# 03_Mos.net
KiCad netlist of a schematic drawn in Altium Designer
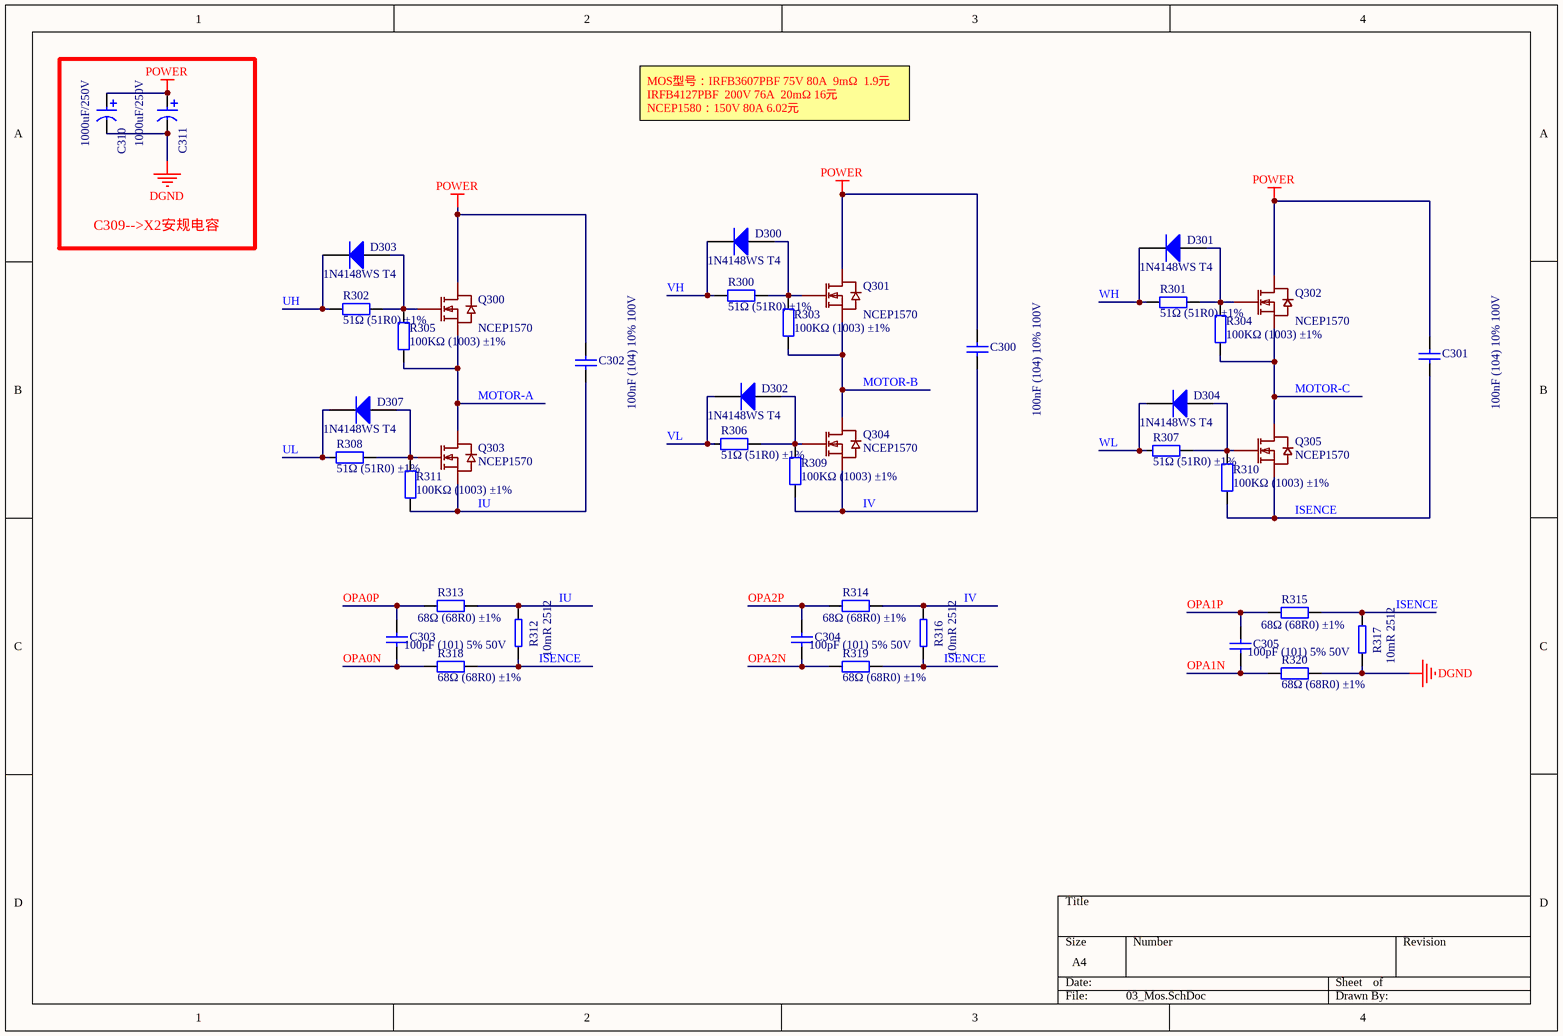
[diagram p0: 03_Mos.SchDoc]

(export (version "E")
  (design (tool "Eeschema 10.0.6"))
  (components
    (comp (ref "C300")
      (value "100nF (104) 10% 100V")
      (footprint "1206_C")
      (description "贴片电容")
      (libsource (lib "Miscellaneous Devices LC") (part "1206 100nF (104) 10% 50V"))
    )
    (comp (ref "C301")
      (value "100nF (104) 10% 100V")
      (footprint "1206_C")
      (description "贴片电容")
      (libsource (lib "Miscellaneous Devices LC") (part "1206 100nF (104) 10% 50V"))
    )
    (comp (ref "C302")
      (value "100nF (104) 10% 100V")
      (footprint "1206_C")
      (description "贴片电容")
      (libsource (lib "Miscellaneous Devices LC") (part "1206 100nF (104) 10% 50V"))
    )
    (comp (ref "C303")
      (value "100pF (101) 5% 50V")
      (footprint "0805_C")
      (description "贴片电容")
      (libsource (lib "Miscellaneous Devices LC") (part "0805 100pF (101) 5% 50V"))
    )
    (comp (ref "C304")
      (value "100pF (101) 5% 50V")
      (footprint "0805_C")
      (description "贴片电容")
      (libsource (lib "Miscellaneous Devices LC") (part "0805 100pF (101) 5% 50V"))
    )
    (comp (ref "C305")
      (value "100pF (101) 5% 50V")
      (footprint "0805_C")
      (description "贴片电容")
      (libsource (lib "Miscellaneous Devices LC") (part "0805 100pF (101) 5% 50V"))
    )
    (comp (ref "C310")
      (value "1000uF/250V")
      (footprint "1000uf/250V")
      (description "电解电容")
      (libsource (lib "Schlibv2") (part "CAP2"))
    )
    (comp (ref "C311")
      (value "1000uF/250V")
      (footprint "1000uf/250V")
      (description "电解电容")
      (libsource (lib "Schlibv2") (part "CAP2"))
    )
    (comp (ref "D300")
      (value "1N4148WS T4")
      (footprint "SOD-323")
      (description "二极管")
      (libsource (lib "Miscellaneous Devices LC") (part "SOD-323 1N4148WS T4"))
    )
    (comp (ref "D301")
      (value "1N4148WS T4")
      (footprint "SOD-323")
      (description "二极管")
      (libsource (lib "Miscellaneous Devices LC") (part "SOD-323 1N4148WS T4"))
    )
    (comp (ref "D302")
      (value "1N4148WS T4")
      (footprint "SOD-323")
      (description "二极管")
      (libsource (lib "Miscellaneous Devices LC") (part "SOD-323 1N4148WS T4"))
    )
    (comp (ref "D303")
      (value "1N4148WS T4")
      (footprint "SOD-323")
      (description "二极管")
      (libsource (lib "Miscellaneous Devices LC") (part "SOD-323 1N4148WS T4"))
    )
    (comp (ref "D304")
      (value "1N4148WS T4")
      (footprint "SOD-323")
      (description "二极管")
      (libsource (lib "Miscellaneous Devices LC") (part "SOD-323 1N4148WS T4"))
    )
    (comp (ref "D307")
      (value "1N4148WS T4")
      (footprint "SOD-323")
      (description "二极管")
      (libsource (lib "Miscellaneous Devices LC") (part "SOD-323 1N4148WS T4"))
    )
    (comp (ref "Q300")
      (value "NCEP1570")
      (footprint "IRFB4127")
      (libsource (lib "RayPCB20210502") (part "IRFB4127PBF"))
    )
    (comp (ref "Q301")
      (value "NCEP1570")
      (footprint "IRFB4127")
      (libsource (lib "RayPCB20210502") (part "IRFB4127PBF"))
    )
    (comp (ref "Q302")
      (value "NCEP1570")
      (footprint "IRFB4127")
      (libsource (lib "RayPCB20210502") (part "IRFB4127PBF"))
    )
    (comp (ref "Q303")
      (value "NCEP1570")
      (footprint "IRFB4127")
      (libsource (lib "RayPCB20210502") (part "IRFB4127PBF"))
    )
    (comp (ref "Q304")
      (value "NCEP1570")
      (footprint "IRFB4127")
      (libsource (lib "RayPCB20210502") (part "IRFB4127PBF"))
    )
    (comp (ref "Q305")
      (value "NCEP1570")
      (footprint "IRFB4127")
      (libsource (lib "RayPCB20210502") (part "IRFB4127PBF"))
    )
    (comp (ref "R300")
      (value "51Ω (51R0) ±1%")
      (footprint "0805_R")
      (description "贴片电阻")
      (libsource (lib "Miscellaneous Devices LC") (part "0805 51Ω (51R0) 1%"))
    )
    (comp (ref "R301")
      (value "51Ω (51R0) ±1%")
      (footprint "0805_R")
      (description "贴片电阻")
      (libsource (lib "Miscellaneous Devices LC") (part "0805 51Ω (51R0) 1%"))
    )
    (comp (ref "R302")
      (value "51Ω (51R0) ±1%")
      (footprint "0805_R")
      (description "贴片电阻")
      (libsource (lib "Miscellaneous Devices LC") (part "0805 51Ω (51R0) 1%"))
    )
    (comp (ref "R303")
      (value "100KΩ (1003) ±1%")
      (footprint "0805_R")
      (description "贴片电阻")
      (libsource (lib "Miscellaneous Devices LC") (part "0805 100KΩ (1003) 1%"))
    )
    (comp (ref "R304")
      (value "100KΩ (1003) ±1%")
      (footprint "0805_R")
      (description "贴片电阻")
      (libsource (lib "Miscellaneous Devices LC") (part "0805 100KΩ (1003) 1%"))
    )
    (comp (ref "R305")
      (value "100KΩ (1003) ±1%")
      (footprint "0805_R")
      (description "贴片电阻")
      (libsource (lib "Miscellaneous Devices LC") (part "0805 100KΩ (1003) 1%"))
    )
    (comp (ref "R306")
      (value "51Ω (51R0) ±1%")
      (footprint "0805_R")
      (description "贴片电阻")
      (libsource (lib "Miscellaneous Devices LC") (part "0805 51Ω (51R0) 1%"))
    )
    (comp (ref "R307")
      (value "51Ω (51R0) ±1%")
      (footprint "0805_R")
      (description "贴片电阻")
      (libsource (lib "Miscellaneous Devices LC") (part "0805 51Ω (51R0) 1%"))
    )
    (comp (ref "R308")
      (value "51Ω (51R0) ±1%")
      (footprint "0805_R")
      (description "贴片电阻")
      (libsource (lib "Miscellaneous Devices LC") (part "0805 51Ω (51R0) 1%"))
    )
    (comp (ref "R309")
      (value "100KΩ (1003) ±1%")
      (footprint "0805_R")
      (description "贴片电阻")
      (libsource (lib "Miscellaneous Devices LC") (part "0805 100KΩ (1003) 1%"))
    )
    (comp (ref "R310")
      (value "100KΩ (1003) ±1%")
      (footprint "0805_R")
      (description "贴片电阻")
      (libsource (lib "Miscellaneous Devices LC") (part "0805 100KΩ (1003) 1%"))
    )
    (comp (ref "R311")
      (value "100KΩ (1003) ±1%")
      (footprint "0805_R")
      (description "贴片电阻")
      (libsource (lib "Miscellaneous Devices LC") (part "0805 100KΩ (1003) 1%"))
    )
    (comp (ref "R312")
      (value "10mR 2512")
      (footprint "R2512")
      (libsource (lib "RayPCB20210502") (part "Res10K"))
    )
    (comp (ref "R313")
      (value "68Ω (68R0) ±1%")
      (footprint "0805_R")
      (description "贴片电阻")
      (libsource (lib "Miscellaneous Devices LC") (part "0805 68Ω (68R0) 1%"))
    )
    (comp (ref "R314")
      (value "68Ω (68R0) ±1%")
      (footprint "0805_R")
      (description "贴片电阻")
      (libsource (lib "Miscellaneous Devices LC") (part "0805 68Ω (68R0) 1%"))
    )
    (comp (ref "R315")
      (value "68Ω (68R0) ±1%")
      (footprint "0805_R")
      (description "贴片电阻")
      (libsource (lib "Miscellaneous Devices LC") (part "0805 68Ω (68R0) 1%"))
    )
    (comp (ref "R316")
      (value "10mR 2512")
      (footprint "R2512")
      (libsource (lib "RayPCB20210502") (part "Res10K"))
    )
    (comp (ref "R317")
      (value "10mR 2512")
      (footprint "R2512")
      (libsource (lib "RayPCB20210502") (part "Res10K"))
    )
    (comp (ref "R318")
      (value "68Ω (68R0) ±1%")
      (footprint "0805_R")
      (description "贴片电阻")
      (libsource (lib "Miscellaneous Devices LC") (part "0805 68Ω (68R0) 1%"))
    )
    (comp (ref "R319")
      (value "68Ω (68R0) ±1%")
      (footprint "0805_R")
      (description "贴片电阻")
      (libsource (lib "Miscellaneous Devices LC") (part "0805 68Ω (68R0) 1%"))
    )
    (comp (ref "R320")
      (value "68Ω (68R0) ±1%")
      (footprint "0805_R")
      (description "贴片电阻")
      (libsource (lib "Miscellaneous Devices LC") (part "0805 68Ω (68R0) 1%"))
    )
  )
  (nets
    (net (code "1") (name "/ISENCE") (class "Default")
      (node (ref "C301") (pin "1") (pinfunction "1_1") (pintype "passive"))
      (node (ref "Q305") (pin "3") (pinfunction "S_3") (pintype "passive"))
      (node (ref "R310") (pin "1") (pinfunction "1_1") (pintype "passive"))
      (node (ref "R312") (pin "1") (pintype "passive"))
      (node (ref "R315") (pin "2") (pinfunction "2_2") (pintype "passive"))
      (node (ref "R316") (pin "1") (pintype "passive"))
      (node (ref "R317") (pin "2") (pintype "passive"))
      (node (ref "R318") (pin "2") (pinfunction "2_2") (pintype "passive"))
      (node (ref "R319") (pin "2") (pinfunction "2_2") (pintype "passive"))
    )
    (net (code "2") (name "/IU") (class "Default")
      (node (ref "C302") (pin "1") (pinfunction "1_1") (pintype "passive"))
      (node (ref "Q303") (pin "3") (pinfunction "S_3") (pintype "passive"))
      (node (ref "R311") (pin "1") (pinfunction "1_1") (pintype "passive"))
      (node (ref "R312") (pin "2") (pintype "passive"))
      (node (ref "R313") (pin "2") (pinfunction "2_2") (pintype "passive"))
    )
    (net (code "3") (name "/IV") (class "Default")
      (node (ref "C300") (pin "1") (pinfunction "1_1") (pintype "passive"))
      (node (ref "Q304") (pin "3") (pinfunction "S_3") (pintype "passive"))
      (node (ref "R309") (pin "1") (pinfunction "1_1") (pintype "passive"))
      (node (ref "R314") (pin "2") (pinfunction "2_2") (pintype "passive"))
      (node (ref "R316") (pin "2") (pintype "passive"))
    )
    (net (code "4") (name "/MOTOR-A") (class "Default")
      (node (ref "Q300") (pin "3") (pinfunction "S_3") (pintype "passive"))
      (node (ref "Q303") (pin "2") (pinfunction "D_2") (pintype "passive"))
      (node (ref "R305") (pin "1") (pinfunction "1_1") (pintype "passive"))
    )
    (net (code "5") (name "/MOTOR-B") (class "Default")
      (node (ref "Q301") (pin "3") (pinfunction "S_3") (pintype "passive"))
      (node (ref "Q304") (pin "2") (pinfunction "D_2") (pintype "passive"))
      (node (ref "R303") (pin "1") (pinfunction "1_1") (pintype "passive"))
    )
    (net (code "6") (name "/MOTOR-C") (class "Default")
      (node (ref "Q302") (pin "3") (pinfunction "S_3") (pintype "passive"))
      (node (ref "Q305") (pin "2") (pinfunction "D_2") (pintype "passive"))
      (node (ref "R304") (pin "1") (pinfunction "1_1") (pintype "passive"))
    )
    (net (code "7") (name "/OPA0N") (class "Default")
      (node (ref "C303") (pin "1") (pinfunction "1_1") (pintype "passive"))
      (node (ref "R318") (pin "1") (pinfunction "1_1") (pintype "passive"))
    )
    (net (code "8") (name "/OPA0P") (class "Default")
      (node (ref "C303") (pin "2") (pinfunction "2_2") (pintype "passive"))
      (node (ref "R313") (pin "1") (pinfunction "1_1") (pintype "passive"))
    )
    (net (code "9") (name "/OPA1N") (class "Default")
      (node (ref "C305") (pin "1") (pinfunction "1_1") (pintype "passive"))
      (node (ref "R320") (pin "1") (pinfunction "1_1") (pintype "passive"))
    )
    (net (code "10") (name "/OPA1P") (class "Default")
      (node (ref "C305") (pin "2") (pinfunction "2_2") (pintype "passive"))
      (node (ref "R315") (pin "1") (pinfunction "1_1") (pintype "passive"))
    )
    (net (code "11") (name "/OPA2N") (class "Default")
      (node (ref "C304") (pin "1") (pinfunction "1_1") (pintype "passive"))
      (node (ref "R319") (pin "1") (pinfunction "1_1") (pintype "passive"))
    )
    (net (code "12") (name "/OPA2P") (class "Default")
      (node (ref "C304") (pin "2") (pinfunction "2_2") (pintype "passive"))
      (node (ref "R314") (pin "1") (pinfunction "1_1") (pintype "passive"))
    )
    (net (code "13") (name "/UH") (class "Default")
      (node (ref "D303") (pin "2") (pinfunction "K_2") (pintype "passive"))
      (node (ref "R302") (pin "1") (pinfunction "1_1") (pintype "passive"))
    )
    (net (code "14") (name "/UL") (class "Default")
      (node (ref "D307") (pin "2") (pinfunction "K_2") (pintype "passive"))
      (node (ref "R308") (pin "1") (pinfunction "1_1") (pintype "passive"))
    )
    (net (code "15") (name "/VH") (class "Default")
      (node (ref "D300") (pin "2") (pinfunction "K_2") (pintype "passive"))
      (node (ref "R300") (pin "1") (pinfunction "1_1") (pintype "passive"))
    )
    (net (code "16") (name "/VL") (class "Default")
      (node (ref "D302") (pin "2") (pinfunction "K_2") (pintype "passive"))
      (node (ref "R306") (pin "1") (pinfunction "1_1") (pintype "passive"))
    )
    (net (code "17") (name "/WH") (class "Default")
      (node (ref "D301") (pin "2") (pinfunction "K_2") (pintype "passive"))
      (node (ref "R301") (pin "1") (pinfunction "1_1") (pintype "passive"))
    )
    (net (code "18") (name "/WL") (class "Default")
      (node (ref "D304") (pin "2") (pinfunction "K_2") (pintype "passive"))
      (node (ref "R307") (pin "1") (pinfunction "1_1") (pintype "passive"))
    )
    (net (code "19") (name "DGND") (class "Default")
      (node (ref "C310") (pin "2") (pintype "passive"))
      (node (ref "C311") (pin "2") (pintype "passive"))
      (node (ref "R317") (pin "1") (pintype "passive"))
      (node (ref "R320") (pin "2") (pinfunction "2_2") (pintype "passive"))
    )
    (net (code "20") (name "Net-(D300-A)") (class "Default")
      (node (ref "D300") (pin "1") (pinfunction "A_1") (pintype "passive"))
      (node (ref "Q301") (pin "1") (pinfunction "G_1") (pintype "passive"))
      (node (ref "R300") (pin "2") (pinfunction "2_2") (pintype "passive"))
      (node (ref "R303") (pin "2") (pinfunction "2_2") (pintype "passive"))
    )
    (net (code "21") (name "Net-(D301-A)") (class "Default")
      (node (ref "D301") (pin "1") (pinfunction "A_1") (pintype "passive"))
      (node (ref "Q302") (pin "1") (pinfunction "G_1") (pintype "passive"))
      (node (ref "R301") (pin "2") (pinfunction "2_2") (pintype "passive"))
      (node (ref "R304") (pin "2") (pinfunction "2_2") (pintype "passive"))
    )
    (net (code "22") (name "Net-(D302-A)") (class "Default")
      (node (ref "D302") (pin "1") (pinfunction "A_1") (pintype "passive"))
      (node (ref "Q304") (pin "1") (pinfunction "G_1") (pintype "passive"))
      (node (ref "R306") (pin "2") (pinfunction "2_2") (pintype "passive"))
      (node (ref "R309") (pin "2") (pinfunction "2_2") (pintype "passive"))
    )
    (net (code "23") (name "Net-(D303-A)") (class "Default")
      (node (ref "D303") (pin "1") (pinfunction "A_1") (pintype "passive"))
      (node (ref "Q300") (pin "1") (pinfunction "G_1") (pintype "passive"))
      (node (ref "R302") (pin "2") (pinfunction "2_2") (pintype "passive"))
      (node (ref "R305") (pin "2") (pinfunction "2_2") (pintype "passive"))
    )
    (net (code "24") (name "Net-(D304-A)") (class "Default")
      (node (ref "D304") (pin "1") (pinfunction "A_1") (pintype "passive"))
      (node (ref "Q305") (pin "1") (pinfunction "G_1") (pintype "passive"))
      (node (ref "R307") (pin "2") (pinfunction "2_2") (pintype "passive"))
      (node (ref "R310") (pin "2") (pinfunction "2_2") (pintype "passive"))
    )
    (net (code "25") (name "Net-(D307-A)") (class "Default")
      (node (ref "D307") (pin "1") (pinfunction "A_1") (pintype "passive"))
      (node (ref "Q303") (pin "1") (pinfunction "G_1") (pintype "passive"))
      (node (ref "R308") (pin "2") (pinfunction "2_2") (pintype "passive"))
      (node (ref "R311") (pin "2") (pinfunction "2_2") (pintype "passive"))
    )
    (net (code "26") (name "POWER") (class "Default")
      (node (ref "C300") (pin "2") (pinfunction "2_2") (pintype "passive"))
      (node (ref "C301") (pin "2") (pinfunction "2_2") (pintype "passive"))
      (node (ref "C302") (pin "2") (pinfunction "2_2") (pintype "passive"))
      (node (ref "C310") (pin "1") (pintype "passive"))
      (node (ref "C311") (pin "1") (pintype "passive"))
      (node (ref "Q300") (pin "2") (pinfunction "D_2") (pintype "passive"))
      (node (ref "Q301") (pin "2") (pinfunction "D_2") (pintype "passive"))
      (node (ref "Q302") (pin "2") (pinfunction "D_2") (pintype "passive"))
    )
  )
)
